# LR_meter.net
KiCad netlist of a schematic drawn in EAGLE
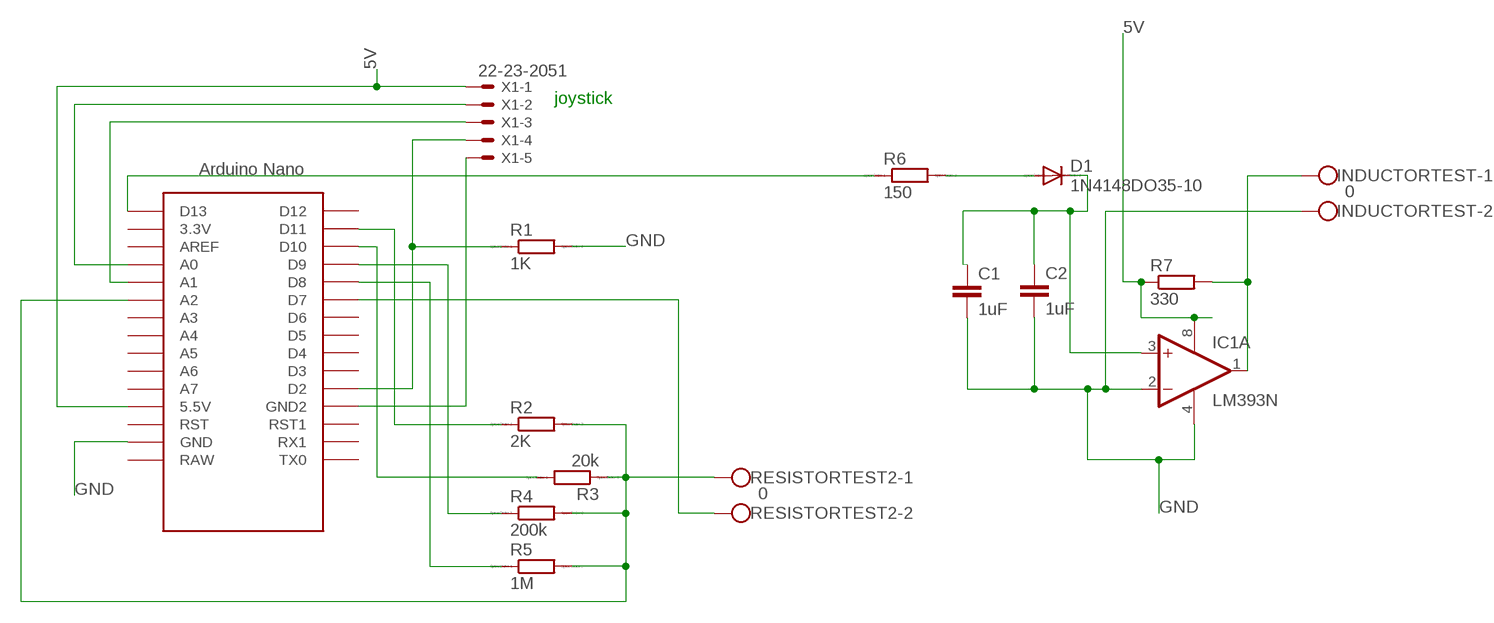
[diagram p0: schematic, sheet 1]

(export (version "E")
  (design (tool "Eeschema 10.0.6"))
  (components
    (comp (ref "C1")
      (value "1uF")
      (footprint "eagle-import:C5B2.5")
      (libsource (lib "eagle-import") (part "C5/2.5"))
    )
    (comp (ref "C2")
      (value "1uF")
      (footprint "eagle-import:C5B2.5")
      (libsource (lib "eagle-import") (part "C5/2.5"))
    )
    (comp (ref "D1")
      (value "1N4148DO35-10")
      (footprint "eagle-import:DO35-10")
      (libsource (lib "eagle-import") (part "1N4148DO35-10"))
    )
    (comp (ref "IC1")
      (value "LM393N")
      (footprint "eagle-import:DIL08")
      (libsource (lib "eagle-import") (part "LM393N"))
    )
    (comp (ref "INDUCTORTEST")
      (value "0")
      (footprint "eagle-import:W237-102")
      (fields (field (name "MPN") "237-102"))
      (libsource (lib "eagle-import") (part "W237-102"))
    )
    (comp (ref "R1")
      (value "1K")
      (footprint "eagle-import:0207_10")
      (libsource (lib "eagle-import") (part "R0207/10"))
    )
    (comp (ref "R2")
      (value "2K")
      (footprint "eagle-import:0207_10")
      (libsource (lib "eagle-import") (part "R0207/10"))
    )
    (comp (ref "R3")
      (value "20k")
      (footprint "eagle-import:0207_10")
      (libsource (lib "eagle-import") (part "R0207/10"))
    )
    (comp (ref "R4")
      (value "200k")
      (footprint "eagle-import:0207_10")
      (libsource (lib "eagle-import") (part "R0207/10"))
    )
    (comp (ref "R5")
      (value "1M")
      (footprint "eagle-import:0207_10")
      (libsource (lib "eagle-import") (part "R0207/10"))
    )
    (comp (ref "R6")
      (value "150")
      (footprint "eagle-import:0207_10")
      (libsource (lib "eagle-import") (part "R0207/10"))
    )
    (comp (ref "R7")
      (value "330")
      (footprint "eagle-import:0207_15")
      (libsource (lib "eagle-import") (part "R-EU_0207/15"))
    )
    (comp (ref "RESISTORTEST2")
      (value "0")
      (footprint "eagle-import:W237-102")
      (fields (field (name "MPN") "237-102"))
      (libsource (lib "eagle-import") (part "W237-102"))
    )
    (comp (ref "U$1")
      (value "NANO")
      (footprint "eagle-import:NANO")
      (libsource (lib "eagle-import") (part "NANO"))
    )
    (comp (ref "X1")
      (value "22-23-2051")
      (footprint "eagle-import:22-23-2051")
      (fields (field (name "MF") "MOLEX"))
      (libsource (lib "eagle-import") (part "22-23-2051"))
    )
  )
  (nets
    (net (code "1") (name "/5V") (class "Default")
      (node (ref "IC1") (pin "8") (pinfunction "V+_8") (pintype "power_in"))
      (node (ref "R7") (pin "1") (pinfunction "1_1") (pintype "passive"))
      (node (ref "U$1") (pin "5V") (pinfunction "5.5V_5V") (pintype "bidirectional"))
      (node (ref "X1") (pin "1") (pinfunction "S_1") (pintype "passive"))
    )
    (net (code "2") (name "/GND") (class "Default")
      (node (ref "C1") (pin "2") (pinfunction "2_2") (pintype "passive"))
      (node (ref "C2") (pin "2") (pinfunction "2_2") (pintype "passive"))
      (node (ref "IC1") (pin "2") (pinfunction "-IN_2") (pintype "input"))
      (node (ref "IC1") (pin "4") (pinfunction "V-_4") (pintype "power_in"))
      (node (ref "INDUCTORTEST") (pin "2") (pinfunction "KL_2") (pintype "passive"))
      (node (ref "R1") (pin "2") (pinfunction "2_2") (pintype "passive"))
      (node (ref "U$1") (pin "GND") (pinfunction "GND_GND") (pintype "bidirectional"))
    )
    (net (code "3") (name "Net-(D1-PadA)") (class "Default")
      (node (ref "D1") (pin "A") (pinfunction "A_A") (pintype "passive"))
      (node (ref "R6") (pin "2") (pinfunction "2_2") (pintype "passive"))
    )
    (net (code "4") (name "Net-(IC1A-+IN)") (class "Default")
      (node (ref "C1") (pin "1") (pinfunction "1_1") (pintype "passive"))
      (node (ref "C2") (pin "1") (pinfunction "1_1") (pintype "passive"))
      (node (ref "D1") (pin "C") (pinfunction "C_C") (pintype "passive"))
      (node (ref "IC1") (pin "3") (pinfunction "+IN_3") (pintype "input"))
    )
    (net (code "5") (name "Net-(IC1A-OUT)") (class "Default")
      (node (ref "IC1") (pin "1") (pinfunction "OUT_1") (pintype "output"))
      (node (ref "INDUCTORTEST") (pin "1") (pinfunction "KL_1") (pintype "passive"))
      (node (ref "R7") (pin "2") (pinfunction "2_2") (pintype "passive"))
    )
    (net (code "6") (name "Net-(R2-Pad1)") (class "Default")
      (node (ref "R2") (pin "1") (pinfunction "1_1") (pintype "passive"))
      (node (ref "U$1") (pin "D11") (pinfunction "D11_D11") (pintype "bidirectional"))
    )
    (net (code "7") (name "Net-(R3-Pad2)") (class "Default")
      (node (ref "R3") (pin "2") (pinfunction "2_2") (pintype "passive"))
      (node (ref "U$1") (pin "D10") (pinfunction "D10_D10") (pintype "bidirectional"))
    )
    (net (code "8") (name "Net-(R4-Pad1)") (class "Default")
      (node (ref "R4") (pin "1") (pinfunction "1_1") (pintype "passive"))
      (node (ref "U$1") (pin "D9") (pinfunction "D9_D9") (pintype "bidirectional"))
    )
    (net (code "9") (name "Net-(R5-Pad1)") (class "Default")
      (node (ref "R5") (pin "1") (pinfunction "1_1") (pintype "passive"))
      (node (ref "U$1") (pin "D8") (pinfunction "D8_D8") (pintype "bidirectional"))
    )
    (net (code "10") (name "Net-(R6-Pad1)") (class "Default")
      (node (ref "R6") (pin "1") (pinfunction "1_1") (pintype "passive"))
      (node (ref "U$1") (pin "D13") (pinfunction "D13_D13") (pintype "bidirectional"))
    )
    (net (code "11") (name "Net-(RESISTORTEST2A-KL)") (class "Default")
      (node (ref "R2") (pin "2") (pinfunction "2_2") (pintype "passive"))
      (node (ref "R3") (pin "1") (pinfunction "1_1") (pintype "passive"))
      (node (ref "R4") (pin "2") (pinfunction "2_2") (pintype "passive"))
      (node (ref "R5") (pin "2") (pinfunction "2_2") (pintype "passive"))
      (node (ref "RESISTORTEST2") (pin "1") (pinfunction "KL_1") (pintype "passive"))
      (node (ref "U$1") (pin "A2") (pinfunction "A2_A2") (pintype "bidirectional"))
    )
    (net (code "12") (name "Net-(RESISTORTEST2B-KL)") (class "Default")
      (node (ref "RESISTORTEST2") (pin "2") (pinfunction "KL_2") (pintype "passive"))
      (node (ref "U$1") (pin "D7") (pinfunction "D7_D7") (pintype "bidirectional"))
    )
    (net (code "13") (name "Net-(U$1-GND2)") (class "Default")
      (node (ref "U$1") (pin "GND1") (pinfunction "GND2_GND1") (pintype "bidirectional"))
      (node (ref "X1") (pin "5") (pinfunction "S_5") (pintype "passive"))
    )
    (net (code "14") (name "Net-(X1B-S)") (class "Default")
      (node (ref "U$1") (pin "A0") (pinfunction "A0_A0") (pintype "bidirectional"))
      (node (ref "X1") (pin "2") (pinfunction "S_2") (pintype "passive"))
    )
    (net (code "15") (name "Net-(X1C-S)") (class "Default")
      (node (ref "U$1") (pin "A1") (pinfunction "A1_A1") (pintype "bidirectional"))
      (node (ref "X1") (pin "3") (pinfunction "S_3") (pintype "passive"))
    )
    (net (code "16") (name "Net-(X1D-S)") (class "Default")
      (node (ref "R1") (pin "1") (pinfunction "1_1") (pintype "passive"))
      (node (ref "U$1") (pin "D2") (pinfunction "D2_D2") (pintype "bidirectional"))
      (node (ref "X1") (pin "4") (pinfunction "S_4") (pintype "passive"))
    )
    (net (code "17") (name "unconnected-(U$1-Pad3.3V)") (class "Default")
      (node (ref "U$1") (pin "3.3V") (pinfunction "3.3V_3.3V") (pintype "bidirectional"))
    )
    (net (code "18") (name "unconnected-(U$1-PadA3)") (class "Default")
      (node (ref "U$1") (pin "A3") (pinfunction "A3_A3") (pintype "bidirectional"))
    )
    (net (code "19") (name "unconnected-(U$1-PadA4)") (class "Default")
      (node (ref "U$1") (pin "A4") (pinfunction "A4_A4") (pintype "bidirectional"))
    )
    (net (code "20") (name "unconnected-(U$1-PadA5)") (class "Default")
      (node (ref "U$1") (pin "A5") (pinfunction "A5_A5") (pintype "bidirectional"))
    )
    (net (code "21") (name "unconnected-(U$1-PadA6)") (class "Default")
      (node (ref "U$1") (pin "A6") (pinfunction "A6_A6") (pintype "bidirectional"))
    )
    (net (code "22") (name "unconnected-(U$1-PadA7)") (class "Default")
      (node (ref "U$1") (pin "A7") (pinfunction "A7_A7") (pintype "bidirectional"))
    )
    (net (code "23") (name "unconnected-(U$1-PadAREF)") (class "Default")
      (node (ref "U$1") (pin "AREF") (pinfunction "AREF_AREF") (pintype "bidirectional"))
    )
    (net (code "24") (name "unconnected-(U$1-PadD3)") (class "Default")
      (node (ref "U$1") (pin "D3") (pinfunction "D3_D3") (pintype "bidirectional"))
    )
    (net (code "25") (name "unconnected-(U$1-PadD4)") (class "Default")
      (node (ref "U$1") (pin "D4") (pinfunction "D4_D4") (pintype "bidirectional"))
    )
    (net (code "26") (name "unconnected-(U$1-PadD5)") (class "Default")
      (node (ref "U$1") (pin "D5") (pinfunction "D5_D5") (pintype "bidirectional"))
    )
    (net (code "27") (name "unconnected-(U$1-PadD6)") (class "Default")
      (node (ref "U$1") (pin "D6") (pinfunction "D6_D6") (pintype "bidirectional"))
    )
    (net (code "28") (name "unconnected-(U$1-PadD12)") (class "Default")
      (node (ref "U$1") (pin "D12") (pinfunction "D12_D12") (pintype "bidirectional"))
    )
    (net (code "29") (name "unconnected-(U$1-PadICSP1)") (class "Default")
      (node (ref "U$1") (pin "ICSP1") (pinfunction "ICSP1_ICSP1") (pintype "bidirectional"))
    )
    (net (code "30") (name "unconnected-(U$1-PadICSP2)") (class "Default")
      (node (ref "U$1") (pin "ICSP2") (pinfunction "ICSP2_ICSP2") (pintype "bidirectional"))
    )
    (net (code "31") (name "unconnected-(U$1-PadICSP3)") (class "Default")
      (node (ref "U$1") (pin "ICSP3") (pinfunction "ICSP3_ICSP3") (pintype "bidirectional"))
    )
    (net (code "32") (name "unconnected-(U$1-PadICSP4)") (class "Default")
      (node (ref "U$1") (pin "ICSP4") (pinfunction "ICSP4_ICSP4") (pintype "bidirectional"))
    )
    (net (code "33") (name "unconnected-(U$1-PadICSP5)") (class "Default")
      (node (ref "U$1") (pin "ICSP5") (pinfunction "ICSP5_ICSP5") (pintype "bidirectional"))
    )
    (net (code "34") (name "unconnected-(U$1-PadICSP6)") (class "Default")
      (node (ref "U$1") (pin "ICSP6") (pinfunction "ICSP6_ICSP6") (pintype "bidirectional"))
    )
    (net (code "35") (name "unconnected-(U$1-PadRAW)") (class "Default")
      (node (ref "U$1") (pin "RAW") (pinfunction "RAW_RAW") (pintype "bidirectional"))
    )
    (net (code "36") (name "unconnected-(U$1-PadRST)") (class "Default")
      (node (ref "U$1") (pin "RST") (pinfunction "RST_RST") (pintype "bidirectional"))
    )
    (net (code "37") (name "unconnected-(U$1-PadRST1)") (class "Default")
      (node (ref "U$1") (pin "RST1") (pinfunction "RST1_RST1") (pintype "bidirectional"))
    )
    (net (code "38") (name "unconnected-(U$1-PadRX1)") (class "Default")
      (node (ref "U$1") (pin "RX1") (pinfunction "RX1_RX1") (pintype "bidirectional"))
    )
    (net (code "39") (name "unconnected-(U$1-PadTX0)") (class "Default")
      (node (ref "U$1") (pin "TX0") (pinfunction "TX0_TX0") (pintype "bidirectional"))
    )
  )
)
